# WT.net
KiCad netlist of a schematic drawn in EAGLE
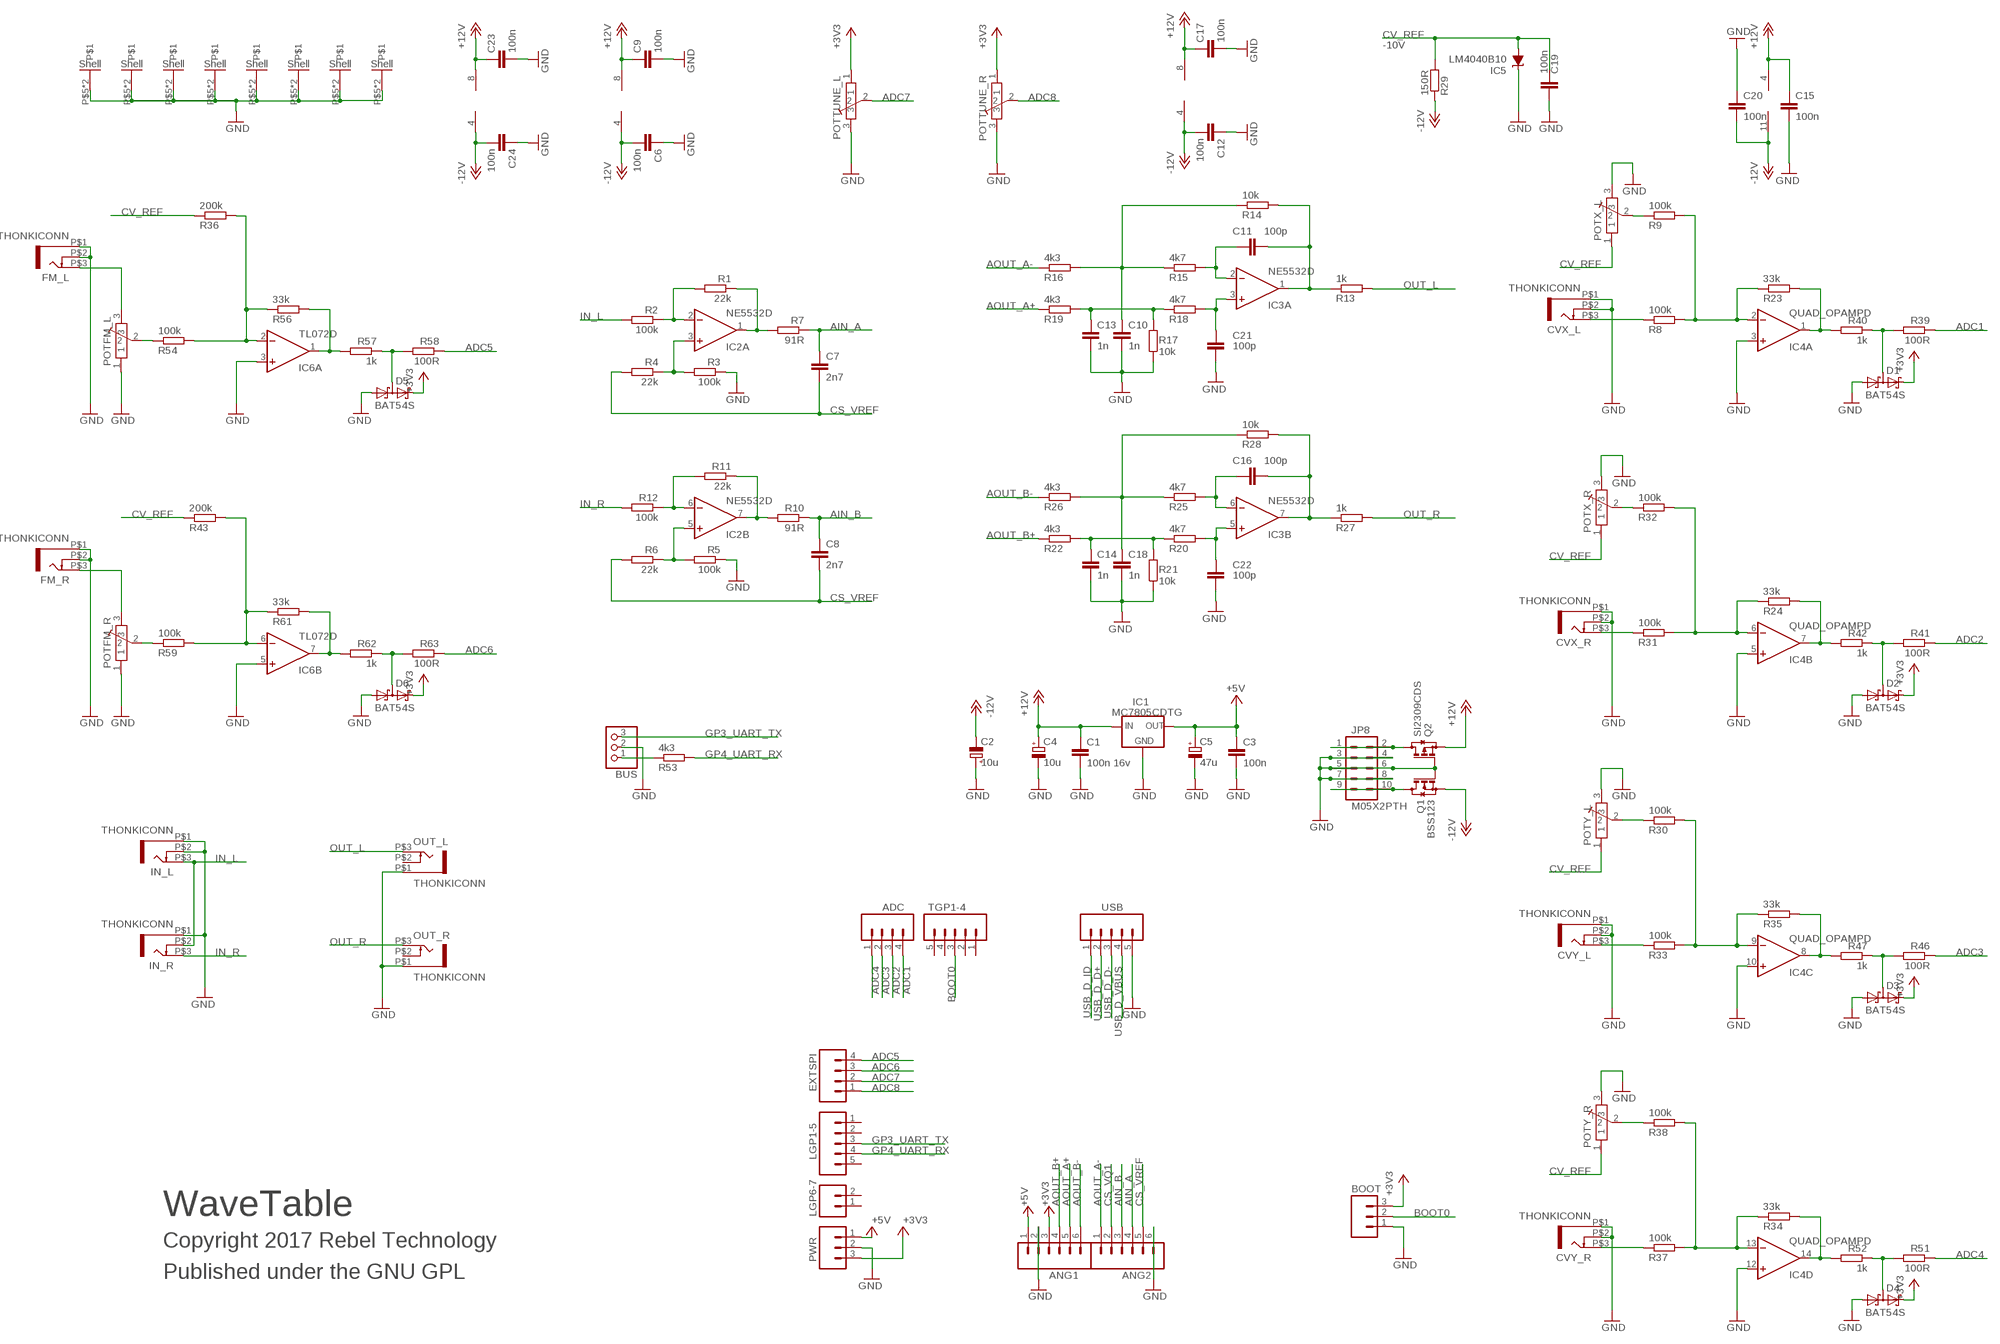
[diagram p0: schematic, sheet 1]

(export (version "E")
  (design (tool "Eeschema 10.0.6"))
  (components
    (comp (ref "ADC")
      (value "M04PTH")
      (footprint "eagle-import:1X04")
      (libsource (lib "eagle-import") (part "M04PTH"))
    )
    (comp (ref "ANG1")
      (value "M06SIP")
      (footprint "eagle-import:1X06")
      (libsource (lib "eagle-import") (part "M06SIP"))
    )
    (comp (ref "ANG2")
      (value "M06SIP")
      (footprint "eagle-import:1X06")
      (libsource (lib "eagle-import") (part "M06SIP"))
    )
    (comp (ref "BOOT")
      (value "M03PTH")
      (footprint "eagle-import:1X03")
      (libsource (lib "eagle-import") (part "M03PTH"))
    )
    (comp (ref "BUS")
      (value "CON-JST-1X03PH-TH")
      (footprint "eagle-import:JST-B3B-PH-KL")
      (libsource (lib "eagle-import") (part "CON-JST-1X03PH-TH"))
    )
    (comp (ref "C1")
      (value "100n 16v")
      (footprint "eagle-import:C0603")
      (libsource (lib "eagle-import") (part "C-EUC0603"))
    )
    (comp (ref "C2")
      (value "10u")
      (footprint "eagle-import:CPOL-5")
      (libsource (lib "eagle-import") (part "CPOL-EU153CLV-0505"))
    )
    (comp (ref "C3")
      (value "100n")
      (footprint "eagle-import:C0603")
      (libsource (lib "eagle-import") (part "C-EUC0603"))
    )
    (comp (ref "C4")
      (value "10u")
      (footprint "eagle-import:CPOL-5")
      (libsource (lib "eagle-import") (part "CPOL-EU153CLV-0505"))
    )
    (comp (ref "C5")
      (value "47u")
      (footprint "eagle-import:PANASONIC_C")
      (libsource (lib "eagle-import") (part "rcl_CPOL-EUC"))
    )
    (comp (ref "C6")
      (value "100n")
      (footprint "eagle-import:C0603")
      (libsource (lib "eagle-import") (part "resistor_C-EUC0603"))
    )
    (comp (ref "C7")
      (value "2n7")
      (footprint "eagle-import:C0603")
      (libsource (lib "eagle-import") (part "resistor_C-EUC0603"))
    )
    (comp (ref "C8")
      (value "2n7")
      (footprint "eagle-import:C0603")
      (libsource (lib "eagle-import") (part "resistor_C-EUC0603"))
    )
    (comp (ref "C9")
      (value "100n")
      (footprint "eagle-import:C0603")
      (libsource (lib "eagle-import") (part "resistor_C-EUC0603"))
    )
    (comp (ref "C10")
      (value "1n")
      (footprint "eagle-import:C0603")
      (libsource (lib "eagle-import") (part "resistor_C-EUC0603"))
    )
    (comp (ref "C11")
      (value "100p")
      (footprint "eagle-import:C0603")
      (libsource (lib "eagle-import") (part "resistor_C-EUC0603"))
    )
    (comp (ref "C12")
      (value "100n")
      (footprint "eagle-import:C0603")
      (libsource (lib "eagle-import") (part "resistor_C-EUC0603"))
    )
    (comp (ref "C13")
      (value "1n")
      (footprint "eagle-import:C0603")
      (libsource (lib "eagle-import") (part "resistor_C-EUC0603"))
    )
    (comp (ref "C14")
      (value "1n")
      (footprint "eagle-import:C0603")
      (libsource (lib "eagle-import") (part "resistor_C-EUC0603"))
    )
    (comp (ref "C15")
      (value "100n")
      (footprint "eagle-import:C0603")
      (libsource (lib "eagle-import") (part "resistor_C-EUC0603"))
    )
    (comp (ref "C16")
      (value "100p")
      (footprint "eagle-import:C0603")
      (libsource (lib "eagle-import") (part "resistor_C-EUC0603"))
    )
    (comp (ref "C17")
      (value "100n")
      (footprint "eagle-import:C0603")
      (libsource (lib "eagle-import") (part "resistor_C-EUC0603"))
    )
    (comp (ref "C18")
      (value "1n")
      (footprint "eagle-import:C0603")
      (libsource (lib "eagle-import") (part "resistor_C-EUC0603"))
    )
    (comp (ref "C19")
      (value "100n")
      (footprint "eagle-import:C0603")
      (libsource (lib "eagle-import") (part "resistor_C-EUC0603"))
    )
    (comp (ref "C20")
      (value "100n")
      (footprint "eagle-import:C0603")
      (libsource (lib "eagle-import") (part "resistor_C-EUC0603"))
    )
    (comp (ref "C21")
      (value "100p")
      (footprint "eagle-import:C0603")
      (libsource (lib "eagle-import") (part "resistor_C-EUC0603"))
    )
    (comp (ref "C22")
      (value "100p")
      (footprint "eagle-import:C0603")
      (libsource (lib "eagle-import") (part "resistor_C-EUC0603"))
    )
    (comp (ref "C23")
      (value "100n")
      (footprint "eagle-import:C0603")
      (libsource (lib "eagle-import") (part "resistor_C-EUC0603"))
    )
    (comp (ref "C24")
      (value "100n")
      (footprint "eagle-import:C0603")
      (libsource (lib "eagle-import") (part "resistor_C-EUC0603"))
    )
    (comp (ref "CVX_L")
      (value "THONKICONN")
      (footprint "eagle-import:THONKICONN")
      (libsource (lib "eagle-import") (part "THONKICONN"))
    )
    (comp (ref "CVX_R")
      (value "THONKICONN")
      (footprint "eagle-import:THONKICONN")
      (libsource (lib "eagle-import") (part "THONKICONN"))
    )
    (comp (ref "CVY_L")
      (value "THONKICONN")
      (footprint "eagle-import:THONKICONN")
      (libsource (lib "eagle-import") (part "THONKICONN"))
    )
    (comp (ref "CVY_R")
      (value "THONKICONN")
      (footprint "eagle-import:THONKICONN")
      (libsource (lib "eagle-import") (part "THONKICONN"))
    )
    (comp (ref "D1")
      (value "BAT54S")
      (footprint "eagle-import:SOT23")
      (libsource (lib "eagle-import") (part "BAT54S"))
    )
    (comp (ref "D2")
      (value "BAT54S")
      (footprint "eagle-import:SOT23")
      (libsource (lib "eagle-import") (part "BAT54S"))
    )
    (comp (ref "D3")
      (value "BAT54S")
      (footprint "eagle-import:SOT23")
      (libsource (lib "eagle-import") (part "BAT54S"))
    )
    (comp (ref "D4")
      (value "BAT54S")
      (footprint "eagle-import:SOT23")
      (libsource (lib "eagle-import") (part "BAT54S"))
    )
    (comp (ref "D5")
      (value "BAT54S")
      (footprint "eagle-import:SOT23")
      (libsource (lib "eagle-import") (part "BAT54S"))
    )
    (comp (ref "D6")
      (value "BAT54S")
      (footprint "eagle-import:SOT23")
      (libsource (lib "eagle-import") (part "BAT54S"))
    )
    (comp (ref "EXTSPI")
      (value "M04PTH")
      (footprint "eagle-import:1X04")
      (libsource (lib "eagle-import") (part "M04PTH"))
    )
    (comp (ref "FM_L")
      (value "THONKICONN")
      (footprint "eagle-import:THONKICONN")
      (libsource (lib "eagle-import") (part "THONKICONN"))
    )
    (comp (ref "FM_R")
      (value "THONKICONN")
      (footprint "eagle-import:THONKICONN")
      (libsource (lib "eagle-import") (part "THONKICONN"))
    )
    (comp (ref "IC1")
      (value "MC7805CDTG")
      (footprint "eagle-import:DPACK")
      (libsource (lib "eagle-import") (part "MC78XX"))
    )
    (comp (ref "IC2")
      (value "NE5532D")
      (footprint "eagle-import:SO08")
      (libsource (lib "eagle-import") (part "NE5532D"))
    )
    (comp (ref "IC3")
      (value "NE5532D")
      (footprint "eagle-import:SO08")
      (libsource (lib "eagle-import") (part "NE5532D"))
    )
    (comp (ref "IC4")
      (value "QUAD_OPAMPD")
      (footprint "eagle-import:SO14")
      (libsource (lib "eagle-import") (part "QUAD_OPAMPD"))
    )
    (comp (ref "IC5")
      (value "LM4040B10")
      (footprint "eagle-import:DBZ_R-PDSO-G3")
      (fields (field (name "MF") "TEXAS INSTRUMENT CONNECTORS") (field (name "MPN") "LM4041C12QDBZT"))
      (libsource (lib "eagle-import") (part "LM4041DBZC12"))
    )
    (comp (ref "IC6")
      (value "TL072D")
      (footprint "eagle-import:SO08")
      (libsource (lib "eagle-import") (part "TL072D"))
    )
    (comp (ref "IN_L")
      (value "THONKICONN")
      (footprint "eagle-import:THONKICONN")
      (libsource (lib "eagle-import") (part "THONKICONN"))
    )
    (comp (ref "IN_R")
      (value "THONKICONN")
      (footprint "eagle-import:THONKICONN")
      (libsource (lib "eagle-import") (part "THONKICONN"))
    )
    (comp (ref "JP8")
      (value "M05X2PTH")
      (footprint "eagle-import:AVR_ICSP")
      (libsource (lib "eagle-import") (part "M05X2PTH"))
    )
    (comp (ref "LGP1-5")
      (value "M05PTH")
      (footprint "eagle-import:1X05")
      (libsource (lib "eagle-import") (part "M05PTH"))
    )
    (comp (ref "LGP6-7")
      (value "M02PTH")
      (footprint "eagle-import:1X02")
      (libsource (lib "eagle-import") (part "M02PTH"))
    )
    (comp (ref "OUT_L")
      (value "THONKICONN")
      (footprint "eagle-import:THONKICONN")
      (libsource (lib "eagle-import") (part "THONKICONN"))
    )
    (comp (ref "OUT_R")
      (value "THONKICONN")
      (footprint "eagle-import:THONKICONN")
      (libsource (lib "eagle-import") (part "THONKICONN"))
    )
    (comp (ref "POTFM_L")
      (value "POT-ALPS-RK09L1140")
      (footprint "eagle-import:POT-ALPS-RK09L1140")
      (libsource (lib "eagle-import") (part "POT-ALPS-RK09L1140"))
    )
    (comp (ref "POTFM_R")
      (value "POT-ALPS-RK09L1140")
      (footprint "eagle-import:POT-ALPS-RK09L1140")
      (libsource (lib "eagle-import") (part "POT-ALPS-RK09L1140"))
    )
    (comp (ref "POTTUNE_L")
      (value "POT-ALPS-RK09L1140")
      (footprint "eagle-import:POT-ALPS-RK09L1140")
      (libsource (lib "eagle-import") (part "POT-ALPS-RK09L1140"))
    )
    (comp (ref "POTTUNE_R")
      (value "POT-ALPS-RK09L1140")
      (footprint "eagle-import:POT-ALPS-RK09L1140")
      (libsource (lib "eagle-import") (part "POT-ALPS-RK09L1140"))
    )
    (comp (ref "POTX_L")
      (value "POT-ALPS-RK09L1140")
      (footprint "eagle-import:POT-ALPS-RK09L1140")
      (libsource (lib "eagle-import") (part "POT-ALPS-RK09L1140"))
    )
    (comp (ref "POTX_R")
      (value "POT-ALPS-RK09L1140")
      (footprint "eagle-import:POT-ALPS-RK09L1140")
      (libsource (lib "eagle-import") (part "POT-ALPS-RK09L1140"))
    )
    (comp (ref "POTY_L")
      (value "POT-ALPS-RK09L1140")
      (footprint "eagle-import:POT-ALPS-RK09L1140")
      (libsource (lib "eagle-import") (part "POT-ALPS-RK09L1140"))
    )
    (comp (ref "POTY_R")
      (value "POT-ALPS-RK09L1140")
      (footprint "eagle-import:POT-ALPS-RK09L1140")
      (libsource (lib "eagle-import") (part "POT-ALPS-RK09L1140"))
    )
    (comp (ref "PWR")
      (value "M03PTH")
      (footprint "eagle-import:1X03")
      (libsource (lib "eagle-import") (part "M03PTH"))
    )
    (comp (ref "Q1")
      (value "BSS123")
      (footprint "eagle-import:SOT23")
      (libsource (lib "eagle-import") (part "BSS123"))
    )
    (comp (ref "Q2")
      (value "SI2309CDS")
      (footprint "eagle-import:SOT23")
      (libsource (lib "eagle-import") (part "BSS84"))
    )
    (comp (ref "R1")
      (value "22k")
      (footprint "eagle-import:0603")
      (libsource (lib "eagle-import") (part "R-EU_0603"))
    )
    (comp (ref "R2")
      (value "100k")
      (footprint "eagle-import:0603")
      (libsource (lib "eagle-import") (part "R-EU_0603"))
    )
    (comp (ref "R3")
      (value "100k")
      (footprint "eagle-import:0603")
      (libsource (lib "eagle-import") (part "R-EU_0603"))
    )
    (comp (ref "R4")
      (value "22k")
      (footprint "eagle-import:0603")
      (libsource (lib "eagle-import") (part "R-EU_0603"))
    )
    (comp (ref "R5")
      (value "100k")
      (footprint "eagle-import:0603")
      (libsource (lib "eagle-import") (part "R-EU_0603"))
    )
    (comp (ref "R6")
      (value "22k")
      (footprint "eagle-import:0603")
      (libsource (lib "eagle-import") (part "R-EU_0603"))
    )
    (comp (ref "R7")
      (value "91R")
      (footprint "eagle-import:0603")
      (libsource (lib "eagle-import") (part "R-EU_0603"))
    )
    (comp (ref "R8")
      (value "100k")
      (footprint "eagle-import:0603")
      (libsource (lib "eagle-import") (part "R-EU_0603"))
    )
    (comp (ref "R9")
      (value "100k")
      (footprint "eagle-import:0603")
      (libsource (lib "eagle-import") (part "R-EU_0603"))
    )
    (comp (ref "R10")
      (value "91R")
      (footprint "eagle-import:0603")
      (libsource (lib "eagle-import") (part "R-EU_0603"))
    )
    (comp (ref "R11")
      (value "22k")
      (footprint "eagle-import:0603")
      (libsource (lib "eagle-import") (part "R-EU_0603"))
    )
    (comp (ref "R12")
      (value "100k")
      (footprint "eagle-import:0603")
      (libsource (lib "eagle-import") (part "R-EU_0603"))
    )
    (comp (ref "R13")
      (value "1k")
      (footprint "eagle-import:0603")
      (libsource (lib "eagle-import") (part "R-EU_0603"))
    )
    (comp (ref "R14")
      (value "10k")
      (footprint "eagle-import:0603")
      (libsource (lib "eagle-import") (part "R-EU_0603"))
    )
    (comp (ref "R15")
      (value "4k7")
      (footprint "eagle-import:0603")
      (libsource (lib "eagle-import") (part "R-EU_0603"))
    )
    (comp (ref "R16")
      (value "4k3")
      (footprint "eagle-import:0603")
      (libsource (lib "eagle-import") (part "R-EU_0603"))
    )
    (comp (ref "R17")
      (value "10k")
      (footprint "eagle-import:0603")
      (libsource (lib "eagle-import") (part "R-EU_0603"))
    )
    (comp (ref "R18")
      (value "4k7")
      (footprint "eagle-import:0603")
      (libsource (lib "eagle-import") (part "R-EU_0603"))
    )
    (comp (ref "R19")
      (value "4k3")
      (footprint "eagle-import:0603")
      (libsource (lib "eagle-import") (part "R-EU_0603"))
    )
    (comp (ref "R20")
      (value "4k7")
      (footprint "eagle-import:0603")
      (libsource (lib "eagle-import") (part "R-EU_0603"))
    )
    (comp (ref "R21")
      (value "10k")
      (footprint "eagle-import:0603")
      (libsource (lib "eagle-import") (part "R-EU_0603"))
    )
    (comp (ref "R22")
      (value "4k3")
      (footprint "eagle-import:0603")
      (libsource (lib "eagle-import") (part "R-EU_0603"))
    )
    (comp (ref "R23")
      (value "33k")
      (footprint "eagle-import:0603")
      (libsource (lib "eagle-import") (part "R-EU_0603"))
    )
    (comp (ref "R24")
      (value "33k")
      (footprint "eagle-import:0603")
      (libsource (lib "eagle-import") (part "R-EU_0603"))
    )
    (comp (ref "R25")
      (value "4k7")
      (footprint "eagle-import:0603")
      (libsource (lib "eagle-import") (part "R-EU_0603"))
    )
    (comp (ref "R26")
      (value "4k3")
      (footprint "eagle-import:0603")
      (libsource (lib "eagle-import") (part "R-EU_0603"))
    )
    (comp (ref "R27")
      (value "1k")
      (footprint "eagle-import:0603")
      (libsource (lib "eagle-import") (part "R-EU_0603"))
    )
    (comp (ref "R28")
      (value "10k")
      (footprint "eagle-import:0603")
      (libsource (lib "eagle-import") (part "R-EU_0603"))
    )
    (comp (ref "R29")
      (value "150R")
      (footprint "eagle-import:0603")
      (libsource (lib "eagle-import") (part "R-EU_0603"))
    )
    (comp (ref "R30")
      (value "100k")
      (footprint "eagle-import:0603")
      (libsource (lib "eagle-import") (part "R-EU_0603"))
    )
    (comp (ref "R31")
      (value "100k")
      (footprint "eagle-import:0603")
      (libsource (lib "eagle-import") (part "R-EU_0603"))
    )
    (comp (ref "R32")
      (value "100k")
      (footprint "eagle-import:0603")
      (libsource (lib "eagle-import") (part "R-EU_0603"))
    )
    (comp (ref "R33")
      (value "100k")
      (footprint "eagle-import:0603")
      (libsource (lib "eagle-import") (part "R-EU_0603"))
    )
    (comp (ref "R34")
      (value "33k")
      (footprint "eagle-import:0603")
      (libsource (lib "eagle-import") (part "R-EU_0603"))
    )
    (comp (ref "R35")
      (value "33k")
      (footprint "eagle-import:0603")
      (libsource (lib "eagle-import") (part "R-EU_0603"))
    )
    (comp (ref "R36")
      (value "200k")
      (footprint "eagle-import:0603")
      (libsource (lib "eagle-import") (part "R-EU_0603"))
    )
    (comp (ref "R37")
      (value "100k")
      (footprint "eagle-import:0603")
      (libsource (lib "eagle-import") (part "R-EU_0603"))
    )
    (comp (ref "R38")
      (value "100k")
      (footprint "eagle-import:0603")
      (libsource (lib "eagle-import") (part "R-EU_0603"))
    )
    (comp (ref "R39")
      (value "100R")
      (footprint "eagle-import:0603")
      (libsource (lib "eagle-import") (part "R-EU_0603"))
    )
    (comp (ref "R40")
      (value "1k")
      (footprint "eagle-import:0603")
      (libsource (lib "eagle-import") (part "R-EU_0603"))
    )
    (comp (ref "R41")
      (value "100R")
      (footprint "eagle-import:0603")
      (libsource (lib "eagle-import") (part "R-EU_0603"))
    )
    (comp (ref "R42")
      (value "1k")
      (footprint "eagle-import:0603")
      (libsource (lib "eagle-import") (part "R-EU_0603"))
    )
    (comp (ref "R43")
      (value "200k")
      (footprint "eagle-import:0603")
      (libsource (lib "eagle-import") (part "R-EU_0603"))
    )
    (comp (ref "R46")
      (value "100R")
      (footprint "eagle-import:0603")
      (libsource (lib "eagle-import") (part "R-EU_0603"))
    )
    (comp (ref "R47")
      (value "1k")
      (footprint "eagle-import:0603")
      (libsource (lib "eagle-import") (part "R-EU_0603"))
    )
    (comp (ref "R51")
      (value "100R")
      (footprint "eagle-import:0603")
      (libsource (lib "eagle-import") (part "R-EU_0603"))
    )
    (comp (ref "R52")
      (value "1k")
      (footprint "eagle-import:0603")
      (libsource (lib "eagle-import") (part "R-EU_0603"))
    )
    (comp (ref "R53")
      (value "4k3")
      (footprint "eagle-import:0603")
      (libsource (lib "eagle-import") (part "R-EU_0603"))
    )
    (comp (ref "R54")
      (value "100k")
      (footprint "eagle-import:0603")
      (libsource (lib "eagle-import") (part "R-EU_0603"))
    )
    (comp (ref "R56")
      (value "33k")
      (footprint "eagle-import:0603")
      (libsource (lib "eagle-import") (part "R-EU_0603"))
    )
    (comp (ref "R57")
      (value "1k")
      (footprint "eagle-import:0603")
      (libsource (lib "eagle-import") (part "R-EU_0603"))
    )
    (comp (ref "R58")
      (value "100R")
      (footprint "eagle-import:0603")
      (libsource (lib "eagle-import") (part "R-EU_0603"))
    )
    (comp (ref "R59")
      (value "100k")
      (footprint "eagle-import:0603")
      (libsource (lib "eagle-import") (part "R-EU_0603"))
    )
    (comp (ref "R61")
      (value "33k")
      (footprint "eagle-import:0603")
      (libsource (lib "eagle-import") (part "R-EU_0603"))
    )
    (comp (ref "R62")
      (value "1k")
      (footprint "eagle-import:0603")
      (libsource (lib "eagle-import") (part "R-EU_0603"))
    )
    (comp (ref "R63")
      (value "100R")
      (footprint "eagle-import:0603")
      (libsource (lib "eagle-import") (part "R-EU_0603"))
    )
    (comp (ref "TGP1-4")
      (value "M05PTH")
      (footprint "eagle-import:1X05")
      (libsource (lib "eagle-import") (part "M05PTH"))
    )
    (comp (ref "USB")
      (value "M05PTH")
      (footprint "eagle-import:1X05")
      (libsource (lib "eagle-import") (part "M05PTH"))
    )
  )
  (nets
    (net (code "1") (name "+3V3") (class "Default")
      (node (ref "ANG1") (pin "3") (pinfunction "3_3") (pintype "passive"))
      (node (ref "BOOT") (pin "3") (pinfunction "3_3") (pintype "passive"))
      (node (ref "D1") (pin "2") (pinfunction "C2_2") (pintype "passive"))
      (node (ref "D2") (pin "2") (pinfunction "C2_2") (pintype "passive"))
      (node (ref "D3") (pin "2") (pinfunction "C2_2") (pintype "passive"))
      (node (ref "D4") (pin "2") (pinfunction "C2_2") (pintype "passive"))
      (node (ref "D5") (pin "2") (pinfunction "C2_2") (pintype "passive"))
      (node (ref "D6") (pin "2") (pinfunction "C2_2") (pintype "passive"))
      (node (ref "POTTUNE_L") (pin "1") (pinfunction "1_1") (pintype "bidirectional"))
      (node (ref "POTTUNE_R") (pin "1") (pinfunction "1_1") (pintype "bidirectional"))
      (node (ref "PWR") (pin "3") (pinfunction "3_3") (pintype "passive"))
    )
    (net (code "2") (name "+5V") (class "Default")
      (node (ref "ANG1") (pin "1") (pinfunction "1_1") (pintype "passive"))
      (node (ref "C3") (pin "1") (pinfunction "1_1") (pintype "passive"))
      (node (ref "C5") (pin "+") (pinfunction "+_+") (pintype "passive"))
      (node (ref "IC1") (pin "3") (pinfunction "OUT_3") (pintype "passive"))
      (node (ref "PWR") (pin "1") (pinfunction "1_1") (pintype "passive"))
    )
    (net (code "3") (name "+12V") (class "Default")
      (node (ref "C1") (pin "1") (pinfunction "1_1") (pintype "passive"))
      (node (ref "C15") (pin "1") (pinfunction "1_1") (pintype "passive"))
      (node (ref "C17") (pin "1") (pinfunction "1_1") (pintype "passive"))
      (node (ref "C23") (pin "1") (pinfunction "1_1") (pintype "passive"))
      (node (ref "C4") (pin "+") (pinfunction "+_+") (pintype "passive"))
      (node (ref "C9") (pin "1") (pinfunction "1_1") (pintype "passive"))
      (node (ref "IC1") (pin "1") (pinfunction "IN_1") (pintype "input"))
      (node (ref "IC2") (pin "8") (pinfunction "V+_8") (pintype "power_in"))
      (node (ref "IC3") (pin "8") (pinfunction "V+_8") (pintype "power_in"))
      (node (ref "IC4") (pin "4") (pinfunction "V+_4") (pintype "power_in"))
      (node (ref "IC6") (pin "8") (pinfunction "V+_8") (pintype "power_in"))
      (node (ref "Q2") (pin "2") (pinfunction "S_2") (pintype "passive"))
    )
    (net (code "4") (name "-12V") (class "Default")
      (node (ref "C12") (pin "2") (pinfunction "2_2") (pintype "passive"))
      (node (ref "C2") (pin "-") (pinfunction "-_-") (pintype "passive"))
      (node (ref "C20") (pin "2") (pinfunction "2_2") (pintype "passive"))
      (node (ref "C24") (pin "2") (pinfunction "2_2") (pintype "passive"))
      (node (ref "C6") (pin "2") (pinfunction "2_2") (pintype "passive"))
      (node (ref "IC2") (pin "4") (pinfunction "V-_4") (pintype "power_in"))
      (node (ref "IC3") (pin "4") (pinfunction "V-_4") (pintype "power_in"))
      (node (ref "IC4") (pin "11") (pinfunction "V-_11") (pintype "power_in"))
      (node (ref "IC6") (pin "4") (pinfunction "V-_4") (pintype "power_in"))
      (node (ref "Q1") (pin "2") (pinfunction "S_2") (pintype "passive"))
      (node (ref "R29") (pin "1") (pinfunction "1_1") (pintype "passive"))
    )
    (net (code "5") (name "/ADC1") (class "Default")
      (node (ref "ADC") (pin "4") (pinfunction "4_4") (pintype "passive"))
      (node (ref "R39") (pin "1") (pinfunction "1_1") (pintype "passive"))
    )
    (net (code "6") (name "/ADC2") (class "Default")
      (node (ref "ADC") (pin "3") (pinfunction "3_3") (pintype "passive"))
      (node (ref "R41") (pin "1") (pinfunction "1_1") (pintype "passive"))
    )
    (net (code "7") (name "/ADC3") (class "Default")
      (node (ref "ADC") (pin "2") (pinfunction "2_2") (pintype "passive"))
      (node (ref "R46") (pin "1") (pinfunction "1_1") (pintype "passive"))
    )
    (net (code "8") (name "/ADC4") (class "Default")
      (node (ref "ADC") (pin "1") (pinfunction "1_1") (pintype "passive"))
      (node (ref "R51") (pin "1") (pinfunction "1_1") (pintype "passive"))
    )
    (net (code "9") (name "/ADC5") (class "Default")
      (node (ref "EXTSPI") (pin "4") (pinfunction "4_4") (pintype "passive"))
      (node (ref "R58") (pin "1") (pinfunction "1_1") (pintype "passive"))
    )
    (net (code "10") (name "/ADC6") (class "Default")
      (node (ref "EXTSPI") (pin "3") (pinfunction "3_3") (pintype "passive"))
      (node (ref "R63") (pin "1") (pinfunction "1_1") (pintype "passive"))
    )
    (net (code "11") (name "/ADC7") (class "Default")
      (node (ref "EXTSPI") (pin "2") (pinfunction "2_2") (pintype "passive"))
      (node (ref "POTTUNE_L") (pin "2") (pinfunction "2_2") (pintype "bidirectional"))
    )
    (net (code "12") (name "/ADC8") (class "Default")
      (node (ref "EXTSPI") (pin "1") (pinfunction "1_1") (pintype "passive"))
      (node (ref "POTTUNE_R") (pin "2") (pinfunction "2_2") (pintype "bidirectional"))
    )
    (net (code "13") (name "/AIN_A") (class "Default")
      (node (ref "ANG2") (pin "4") (pinfunction "4_4") (pintype "passive"))
      (node (ref "C7") (pin "1") (pinfunction "1_1") (pintype "passive"))
      (node (ref "R7") (pin "1") (pinfunction "1_1") (pintype "passive"))
    )
    (net (code "14") (name "/AIN_B") (class "Default")
      (node (ref "ANG2") (pin "3") (pinfunction "3_3") (pintype "passive"))
      (node (ref "C8") (pin "1") (pinfunction "1_1") (pintype "passive"))
      (node (ref "R10") (pin "1") (pinfunction "1_1") (pintype "passive"))
    )
    (net (code "15") (name "/AOUT_A+") (class "Default")
      (node (ref "ANG1") (pin "5") (pinfunction "5_5") (pintype "passive"))
      (node (ref "R19") (pin "1") (pinfunction "1_1") (pintype "passive"))
    )
    (net (code "16") (name "/AOUT_A-") (class "Default")
      (node (ref "ANG2") (pin "1") (pinfunction "1_1") (pintype "passive"))
      (node (ref "R16") (pin "1") (pinfunction "1_1") (pintype "passive"))
    )
    (net (code "17") (name "/AOUT_B+") (class "Default")
      (node (ref "ANG1") (pin "4") (pinfunction "4_4") (pintype "passive"))
      (node (ref "R22") (pin "1") (pinfunction "1_1") (pintype "passive"))
    )
    (net (code "18") (name "/AOUT_B-") (class "Default")
      (node (ref "ANG1") (pin "6") (pinfunction "6_6") (pintype "passive"))
      (node (ref "R26") (pin "1") (pinfunction "1_1") (pintype "passive"))
    )
    (net (code "19") (name "/BOOT0") (class "Default")
      (node (ref "BOOT") (pin "2") (pinfunction "2_2") (pintype "passive"))
      (node (ref "TGP1-4") (pin "3") (pinfunction "3_3") (pintype "passive"))
    )
    (net (code "20") (name "/CS_VQ1") (class "Default")
      (node (ref "ANG2") (pin "2") (pinfunction "2_2") (pintype "passive"))
    )
    (net (code "21") (name "/CS_VREF") (class "Default")
      (node (ref "ANG2") (pin "5") (pinfunction "5_5") (pintype "passive"))
      (node (ref "C7") (pin "2") (pinfunction "2_2") (pintype "passive"))
      (node (ref "C8") (pin "2") (pinfunction "2_2") (pintype "passive"))
      (node (ref "R4") (pin "2") (pinfunction "2_2") (pintype "passive"))
      (node (ref "R6") (pin "2") (pinfunction "2_2") (pintype "passive"))
    )
    (net (code "22") (name "/CV_REF") (class "Default")
      (node (ref "C19") (pin "1") (pinfunction "1_1") (pintype "passive"))
      (node (ref "IC5") (pin "2") (pinfunction "A_2") (pintype "passive"))
      (node (ref "POTX_L") (pin "1") (pinfunction "1_1") (pintype "bidirectional"))
      (node (ref "POTX_R") (pin "1") (pinfunction "1_1") (pintype "bidirectional"))
      (node (ref "POTY_L") (pin "1") (pinfunction "1_1") (pintype "bidirectional"))
      (node (ref "POTY_R") (pin "1") (pinfunction "1_1") (pintype "bidirectional"))
      (node (ref "R29") (pin "2") (pinfunction "2_2") (pintype "passive"))
      (node (ref "R36") (pin "1") (pinfunction "1_1") (pintype "passive"))
      (node (ref "R43") (pin "1") (pinfunction "1_1") (pintype "passive"))
    )
    (net (code "23") (name "/GP3_UART_TX") (class "Default")
      (node (ref "BUS") (pin "3") (pinfunction "3_3") (pintype "passive"))
      (node (ref "LGP1-5") (pin "3") (pinfunction "3_3") (pintype "passive"))
    )
    (net (code "24") (name "/GP4_UART_RX") (class "Default")
      (node (ref "LGP1-5") (pin "4") (pinfunction "4_4") (pintype "passive"))
      (node (ref "R53") (pin "2") (pinfunction "2_2") (pintype "passive"))
    )
    (net (code "25") (name "/IN_L") (class "Default")
      (node (ref "IN_L") (pin "P$3") (pinfunction "3_P$3") (pintype "passive"))
      (node (ref "IN_R") (pin "P$2") (pinfunction "4_P$2") (pintype "passive"))
      (node (ref "R2") (pin "2") (pinfunction "2_2") (pintype "passive"))
    )
    (net (code "26") (name "/IN_R") (class "Default")
      (node (ref "IN_R") (pin "P$3") (pinfunction "3_P$3") (pintype "passive"))
      (node (ref "R12") (pin "2") (pinfunction "2_2") (pintype "passive"))
    )
    (net (code "27") (name "/OUT_L") (class "Default")
      (node (ref "OUT_L") (pin "P$3") (pinfunction "3_P$3") (pintype "passive"))
      (node (ref "R13") (pin "2") (pinfunction "2_2") (pintype "passive"))
    )
    (net (code "28") (name "/OUT_R") (class "Default")
      (node (ref "OUT_R") (pin "P$3") (pinfunction "3_P$3") (pintype "passive"))
      (node (ref "R27") (pin "2") (pinfunction "2_2") (pintype "passive"))
    )
    (net (code "29") (name "/USB_D_D+") (class "Default")
      (node (ref "USB") (pin "2") (pinfunction "2_2") (pintype "passive"))
    )
    (net (code "30") (name "/USB_D_D-") (class "Default")
      (node (ref "USB") (pin "3") (pinfunction "3_3") (pintype "passive"))
    )
    (net (code "31") (name "/USB_D_ID") (class "Default")
      (node (ref "USB") (pin "1") (pinfunction "1_1") (pintype "passive"))
    )
    (net (code "32") (name "/USB_D_VBUS") (class "Default")
      (node (ref "USB") (pin "4") (pinfunction "4_4") (pintype "passive"))
    )
    (net (code "33") (name "GND") (class "Default")
      (node (ref "ANG1") (pin "2") (pinfunction "2_2") (pintype "passive"))
      (node (ref "ANG2") (pin "6") (pinfunction "6_6") (pintype "passive"))
      (node (ref "BOOT") (pin "1") (pinfunction "1_1") (pintype "passive"))
      (node (ref "BUS") (pin "2") (pinfunction "2_2") (pintype "passive"))
      (node (ref "C1") (pin "2") (pinfunction "2_2") (pintype "passive"))
      (node (ref "C10") (pin "2") (pinfunction "2_2") (pintype "passive"))
      (node (ref "C12") (pin "1") (pinfunction "1_1") (pintype "passive"))
      (node (ref "C13") (pin "2") (pinfunction "2_2") (pintype "passive"))
      (node (ref "C14") (pin "2") (pinfunction "2_2") (pintype "passive"))
      (node (ref "C15") (pin "2") (pinfunction "2_2") (pintype "passive"))
      (node (ref "C17") (pin "2") (pinfunction "2_2") (pintype "passive"))
      (node (ref "C18") (pin "2") (pinfunction "2_2") (pintype "passive"))
      (node (ref "C19") (pin "2") (pinfunction "2_2") (pintype "passive"))
      (node (ref "C2") (pin "+") (pinfunction "+_+") (pintype "passive"))
      (node (ref "C20") (pin "1") (pinfunction "1_1") (pintype "passive"))
      (node (ref "C21") (pin "2") (pinfunction "2_2") (pintype "passive"))
      (node (ref "C22") (pin "2") (pinfunction "2_2") (pintype "passive"))
      (node (ref "C23") (pin "2") (pinfunction "2_2") (pintype "passive"))
      (node (ref "C24") (pin "1") (pinfunction "1_1") (pintype "passive"))
      (node (ref "C3") (pin "2") (pinfunction "2_2") (pintype "passive"))
      (node (ref "C4") (pin "-") (pinfunction "-_-") (pintype "passive"))
      (node (ref "C5") (pin "-") (pinfunction "-_-") (pintype "passive"))
      (node (ref "C6") (pin "1") (pinfunction "1_1") (pintype "passive"))
      (node (ref "C9") (pin "2") (pinfunction "2_2") (pintype "passive"))
      (node (ref "CVX_L") (pin "P$1") (pinfunction "5_P$1") (pintype "passive"))
      (node (ref "CVX_L") (pin "P$2") (pinfunction "4_P$2") (pintype "passive"))
      (node (ref "CVX_R") (pin "P$1") (pinfunction "5_P$1") (pintype "passive"))
      (node (ref "CVX_R") (pin "P$2") (pinfunction "4_P$2") (pintype "passive"))
      (node (ref "CVY_L") (pin "P$1") (pinfunction "5_P$1") (pintype "passive"))
      (node (ref "CVY_L") (pin "P$2") (pinfunction "4_P$2") (pintype "passive"))
      (node (ref "CVY_R") (pin "P$1") (pinfunction "5_P$1") (pintype "passive"))
      (node (ref "CVY_R") (pin "P$2") (pinfunction "4_P$2") (pintype "passive"))
      (node (ref "D1") (pin "1") (pinfunction "A1_1") (pintype "passive"))
      (node (ref "D2") (pin "1") (pinfunction "A1_1") (pintype "passive"))
      (node (ref "D3") (pin "1") (pinfunction "A1_1") (pintype "passive"))
      (node (ref "D4") (pin "1") (pinfunction "A1_1") (pintype "passive"))
      (node (ref "D5") (pin "1") (pinfunction "A1_1") (pintype "passive"))
      (node (ref "D6") (pin "1") (pinfunction "A1_1") (pintype "passive"))
      (node (ref "FM_L") (pin "P$1") (pinfunction "5_P$1") (pintype "passive"))
      (node (ref "FM_L") (pin "P$2") (pinfunction "4_P$2") (pintype "passive"))
      (node (ref "FM_R") (pin "P$1") (pinfunction "5_P$1") (pintype "passive"))
      (node (ref "FM_R") (pin "P$2") (pinfunction "4_P$2") (pintype "passive"))
      (node (ref "IC1") (pin "4") (pinfunction "GND_4") (pintype "input"))
      (node (ref "IC4") (pin "10") (pinfunction "+IN_10") (pintype "input"))
      (node (ref "IC4") (pin "12") (pinfunction "+IN_12") (pintype "input"))
      (node (ref "IC4") (pin "3") (pinfunction "+IN_3") (pintype "input"))
      (node (ref "IC4") (pin "5") (pinfunction "+IN_5") (pintype "input"))
      (node (ref "IC5") (pin "1") (pinfunction "C_1") (pintype "passive"))
      (node (ref "IC6") (pin "3") (pinfunction "+IN_3") (pintype "input"))
      (node (ref "IC6") (pin "5") (pinfunction "+IN_5") (pintype "input"))
      (node (ref "IN_L") (pin "P$1") (pinfunction "5_P$1") (pintype "passive"))
      (node (ref "IN_L") (pin "P$2") (pinfunction "4_P$2") (pintype "passive"))
      (node (ref "IN_R") (pin "P$1") (pinfunction "5_P$1") (pintype "passive"))
      (node (ref "JP8") (pin "3") (pinfunction "3_3") (pintype "passive"))
      (node (ref "JP8") (pin "4") (pinfunction "4_4") (pintype "passive"))
      (node (ref "JP8") (pin "5") (pinfunction "5_5") (pintype "passive"))
      (node (ref "JP8") (pin "6") (pinfunction "6_6") (pintype "passive"))
      (node (ref "JP8") (pin "7") (pinfunction "7_7") (pintype "passive"))
      (node (ref "JP8") (pin "8") (pinfunction "8_8") (pintype "passive"))
      (node (ref "OUT_L") (pin "P$1") (pinfunction "5_P$1") (pintype "passive"))
      (node (ref "OUT_R") (pin "P$1") (pinfunction "5_P$1") (pintype "passive"))
      (node (ref "POTFM_L") (pin "1") (pinfunction "1_1") (pintype "bidirectional"))
      (node (ref "POTFM_L") (pin "P$5") (pinfunction "P$1_P$5") (pintype "bidirectional"))
      (node (ref "POTFM_L") (pin "P$6") (pinfunction "P$1_P$6") (pintype "bidirectional"))
      (node (ref "POTFM_R") (pin "1") (pinfunction "1_1") (pintype "bidirectional"))
      (node (ref "POTFM_R") (pin "P$5") (pinfunction "P$1_P$5") (pintype "bidirectional"))
      (node (ref "POTFM_R") (pin "P$6") (pinfunction "P$1_P$6") (pintype "bidirectional"))
      (node (ref "POTTUNE_L") (pin "3") (pinfunction "3_3") (pintype "bidirectional"))
      (node (ref "POTTUNE_L") (pin "P$5") (pinfunction "P$1_P$5") (pintype "bidirectional"))
      (node (ref "POTTUNE_L") (pin "P$6") (pinfunction "P$1_P$6") (pintype "bidirectional"))
      (node (ref "POTTUNE_R") (pin "3") (pinfunction "3_3") (pintype "bidirectional"))
      (node (ref "POTTUNE_R") (pin "P$5") (pinfunction "P$1_P$5") (pintype "bidirectional"))
      (node (ref "POTTUNE_R") (pin "P$6") (pinfunction "P$1_P$6") (pintype "bidirectional"))
      (node (ref "POTX_L") (pin "3") (pinfunction "3_3") (pintype "bidirectional"))
      (node (ref "POTX_L") (pin "P$5") (pinfunction "P$1_P$5") (pintype "bidirectional"))
      (node (ref "POTX_L") (pin "P$6") (pinfunction "P$1_P$6") (pintype "bidirectional"))
      (node (ref "POTX_R") (pin "3") (pinfunction "3_3") (pintype "bidirectional"))
      (node (ref "POTX_R") (pin "P$5") (pinfunction "P$1_P$5") (pintype "bidirectional"))
      (node (ref "POTX_R") (pin "P$6") (pinfunction "P$1_P$6") (pintype "bidirectional"))
      (node (ref "POTY_L") (pin "3") (pinfunction "3_3") (pintype "bidirectional"))
      (node (ref "POTY_L") (pin "P$5") (pinfunction "P$1_P$5") (pintype "bidirectional"))
      (node (ref "POTY_L") (pin "P$6") (pinfunction "P$1_P$6") (pintype "bidirectional"))
      (node (ref "POTY_R") (pin "3") (pinfunction "3_3") (pintype "bidirectional"))
      (node (ref "POTY_R") (pin "P$5") (pinfunction "P$1_P$5") (pintype "bidirectional"))
      (node (ref "POTY_R") (pin "P$6") (pinfunction "P$1_P$6") (pintype "bidirectional"))
      (node (ref "PWR") (pin "2") (pinfunction "2_2") (pintype "passive"))
      (node (ref "Q1") (pin "1") (pinfunction "G_1") (pintype "passive"))
      (node (ref "Q2") (pin "1") (pinfunction "G_1") (pintype "passive"))
      (node (ref "R17") (pin "1") (pinfunction "1_1") (pintype "passive"))
      (node (ref "R21") (pin "1") (pinfunction "1_1") (pintype "passive"))
      (node (ref "R3") (pin "1") (pinfunction "1_1") (pintype "passive"))
      (node (ref "R5") (pin "1") (pinfunction "1_1") (pintype "passive"))
      (node (ref "USB") (pin "5") (pinfunction "5_5") (pintype "passive"))
    )
    (net (code "34") (name "Net-(BUS-Pad1)") (class "Default")
      (node (ref "BUS") (pin "1") (pinfunction "1_1") (pintype "passive"))
      (node (ref "R53") (pin "1") (pinfunction "1_1") (pintype "passive"))
    )
    (net (code "35") (name "Net-(C10-Pad1)") (class "Default")
      (node (ref "C10") (pin "1") (pinfunction "1_1") (pintype "passive"))
      (node (ref "R14") (pin "1") (pinfunction "1_1") (pintype "passive"))
      (node (ref "R15") (pin "1") (pinfunction "1_1") (pintype "passive"))
      (node (ref "R16") (pin "2") (pinfunction "2_2") (pintype "passive"))
    )
    (net (code "36") (name "Net-(C13-Pad1)") (class "Default")
      (node (ref "C13") (pin "1") (pinfunction "1_1") (pintype "passive"))
      (node (ref "R17") (pin "2") (pinfunction "2_2") (pintype "passive"))
      (node (ref "R18") (pin "1") (pinfunction "1_1") (pintype "passive"))
      (node (ref "R19") (pin "2") (pinfunction "2_2") (pintype "passive"))
    )
    (net (code "37") (name "Net-(C14-Pad1)") (class "Default")
      (node (ref "C14") (pin "1") (pinfunction "1_1") (pintype "passive"))
      (node (ref "R20") (pin "1") (pinfunction "1_1") (pintype "passive"))
      (node (ref "R21") (pin "2") (pinfunction "2_2") (pintype "passive"))
      (node (ref "R22") (pin "2") (pinfunction "2_2") (pintype "passive"))
    )
    (net (code "38") (name "Net-(C18-Pad1)") (class "Default")
      (node (ref "C18") (pin "1") (pinfunction "1_1") (pintype "passive"))
      (node (ref "R25") (pin "1") (pinfunction "1_1") (pintype "passive"))
      (node (ref "R26") (pin "2") (pinfunction "2_2") (pintype "passive"))
      (node (ref "R28") (pin "1") (pinfunction "1_1") (pintype "passive"))
    )
    (net (code "39") (name "Net-(CVX_L-3)") (class "Default")
      (node (ref "CVX_L") (pin "P$3") (pinfunction "3_P$3") (pintype "passive"))
      (node (ref "R8") (pin "1") (pinfunction "1_1") (pintype "passive"))
    )
    (net (code "40") (name "Net-(CVX_R-3)") (class "Default")
      (node (ref "CVX_R") (pin "P$3") (pinfunction "3_P$3") (pintype "passive"))
      (node (ref "R31") (pin "1") (pinfunction "1_1") (pintype "passive"))
    )
    (net (code "41") (name "Net-(CVY_L-3)") (class "Default")
      (node (ref "CVY_L") (pin "P$3") (pinfunction "3_P$3") (pintype "passive"))
      (node (ref "R33") (pin "1") (pinfunction "1_1") (pintype "passive"))
    )
    (net (code "42") (name "Net-(CVY_R-3)") (class "Default")
      (node (ref "CVY_R") (pin "P$3") (pinfunction "3_P$3") (pintype "passive"))
      (node (ref "R37") (pin "1") (pinfunction "1_1") (pintype "passive"))
    )
    (net (code "43") (name "Net-(D1-C1A2)") (class "Default")
      (node (ref "D1") (pin "3") (pinfunction "C1A2_3") (pintype "passive"))
      (node (ref "R39") (pin "2") (pinfunction "2_2") (pintype "passive"))
      (node (ref "R40") (pin "1") (pinfunction "1_1") (pintype "passive"))
    )
    (net (code "44") (name "Net-(D2-C1A2)") (class "Default")
      (node (ref "D2") (pin "3") (pinfunction "C1A2_3") (pintype "passive"))
      (node (ref "R41") (pin "2") (pinfunction "2_2") (pintype "passive"))
      (node (ref "R42") (pin "1") (pinfunction "1_1") (pintype "passive"))
    )
    (net (code "45") (name "Net-(D3-C1A2)") (class "Default")
      (node (ref "D3") (pin "3") (pinfunction "C1A2_3") (pintype "passive"))
      (node (ref "R46") (pin "2") (pinfunction "2_2") (pintype "passive"))
      (node (ref "R47") (pin "1") (pinfunction "1_1") (pintype "passive"))
    )
    (net (code "46") (name "Net-(D4-C1A2)") (class "Default")
      (node (ref "D4") (pin "3") (pinfunction "C1A2_3") (pintype "passive"))
      (node (ref "R51") (pin "2") (pinfunction "2_2") (pintype "passive"))
      (node (ref "R52") (pin "1") (pinfunction "1_1") (pintype "passive"))
    )
    (net (code "47") (name "Net-(D5-C1A2)") (class "Default")
      (node (ref "D5") (pin "3") (pinfunction "C1A2_3") (pintype "passive"))
      (node (ref "R57") (pin "1") (pinfunction "1_1") (pintype "passive"))
      (node (ref "R58") (pin "2") (pinfunction "2_2") (pintype "passive"))
    )
    (net (code "48") (name "Net-(D6-C1A2)") (class "Default")
      (node (ref "D6") (pin "3") (pinfunction "C1A2_3") (pintype "passive"))
      (node (ref "R62") (pin "1") (pinfunction "1_1") (pintype "passive"))
      (node (ref "R63") (pin "2") (pinfunction "2_2") (pintype "passive"))
    )
    (net (code "49") (name "Net-(FM_L-3)") (class "Default")
      (node (ref "FM_L") (pin "P$3") (pinfunction "3_P$3") (pintype "passive"))
      (node (ref "POTFM_L") (pin "3") (pinfunction "3_3") (pintype "bidirectional"))
    )
    (net (code "50") (name "Net-(FM_R-3)") (class "Default")
      (node (ref "FM_R") (pin "P$3") (pinfunction "3_P$3") (pintype "passive"))
      (node (ref "POTFM_R") (pin "3") (pinfunction "3_3") (pintype "bidirectional"))
    )
    (net (code "51") (name "Net-(IC2A-+IN)") (class "Default")
      (node (ref "IC2") (pin "3") (pinfunction "+IN_3") (pintype "input"))
      (node (ref "R3") (pin "2") (pinfunction "2_2") (pintype "passive"))
      (node (ref "R4") (pin "1") (pinfunction "1_1") (pintype "passive"))
    )
    (net (code "52") (name "Net-(IC2A--IN)") (class "Default")
      (node (ref "IC2") (pin "2") (pinfunction "-IN_2") (pintype "input"))
      (node (ref "R1") (pin "2") (pinfunction "2_2") (pintype "passive"))
      (node (ref "R2") (pin "1") (pinfunction "1_1") (pintype "passive"))
    )
    (net (code "53") (name "Net-(IC2A-OUT)") (class "Default")
      (node (ref "IC2") (pin "1") (pinfunction "OUT_1") (pintype "output"))
      (node (ref "R1") (pin "1") (pinfunction "1_1") (pintype "passive"))
      (node (ref "R7") (pin "2") (pinfunction "2_2") (pintype "passive"))
    )
    (net (code "54") (name "Net-(IC2B-+IN)") (class "Default")
      (node (ref "IC2") (pin "5") (pinfunction "+IN_5") (pintype "input"))
      (node (ref "R5") (pin "2") (pinfunction "2_2") (pintype "passive"))
      (node (ref "R6") (pin "1") (pinfunction "1_1") (pintype "passive"))
    )
    (net (code "55") (name "Net-(IC2B--IN)") (class "Default")
      (node (ref "IC2") (pin "6") (pinfunction "-IN_6") (pintype "input"))
      (node (ref "R11") (pin "2") (pinfunction "2_2") (pintype "passive"))
      (node (ref "R12") (pin "1") (pinfunction "1_1") (pintype "passive"))
    )
    (net (code "56") (name "Net-(IC2B-OUT)") (class "Default")
      (node (ref "IC2") (pin "7") (pinfunction "OUT_7") (pintype "output"))
      (node (ref "R10") (pin "2") (pinfunction "2_2") (pintype "passive"))
      (node (ref "R11") (pin "1") (pinfunction "1_1") (pintype "passive"))
    )
    (net (code "57") (name "Net-(IC3A-+IN)") (class "Default")
      (node (ref "C21") (pin "1") (pinfunction "1_1") (pintype "passive"))
      (node (ref "IC3") (pin "3") (pinfunction "+IN_3") (pintype "input"))
      (node (ref "R18") (pin "2") (pinfunction "2_2") (pintype "passive"))
    )
    (net (code "58") (name "Net-(IC3A--IN)") (class "Default")
      (node (ref "C11") (pin "1") (pinfunction "1_1") (pintype "passive"))
      (node (ref "IC3") (pin "2") (pinfunction "-IN_2") (pintype "input"))
      (node (ref "R15") (pin "2") (pinfunction "2_2") (pintype "passive"))
    )
    (net (code "59") (name "Net-(IC3A-OUT)") (class "Default")
      (node (ref "C11") (pin "2") (pinfunction "2_2") (pintype "passive"))
      (node (ref "IC3") (pin "1") (pinfunction "OUT_1") (pintype "output"))
      (node (ref "R13") (pin "1") (pinfunction "1_1") (pintype "passive"))
      (node (ref "R14") (pin "2") (pinfunction "2_2") (pintype "passive"))
    )
    (net (code "60") (name "Net-(IC3B-+IN)") (class "Default")
      (node (ref "C22") (pin "1") (pinfunction "1_1") (pintype "passive"))
      (node (ref "IC3") (pin "5") (pinfunction "+IN_5") (pintype "input"))
      (node (ref "R20") (pin "2") (pinfunction "2_2") (pintype "passive"))
    )
    (net (code "61") (name "Net-(IC3B--IN)") (class "Default")
      (node (ref "C16") (pin "1") (pinfunction "1_1") (pintype "passive"))
      (node (ref "IC3") (pin "6") (pinfunction "-IN_6") (pintype "input"))
      (node (ref "R25") (pin "2") (pinfunction "2_2") (pintype "passive"))
    )
    (net (code "62") (name "Net-(IC3B-OUT)") (class "Default")
      (node (ref "C16") (pin "2") (pinfunction "2_2") (pintype "passive"))
      (node (ref "IC3") (pin "7") (pinfunction "OUT_7") (pintype "output"))
      (node (ref "R27") (pin "1") (pinfunction "1_1") (pintype "passive"))
      (node (ref "R28") (pin "2") (pinfunction "2_2") (pintype "passive"))
    )
    (net (code "63") (name "Net-(IC4A--IN)") (class "Default")
      (node (ref "IC4") (pin "2") (pinfunction "-IN_2") (pintype "input"))
      (node (ref "R23") (pin "1") (pinfunction "1_1") (pintype "passive"))
      (node (ref "R8") (pin "2") (pinfunction "2_2") (pintype "passive"))
      (node (ref "R9") (pin "2") (pinfunction "2_2") (pintype "passive"))
    )
    (net (code "64") (name "Net-(IC4A-OUT)") (class "Default")
      (node (ref "IC4") (pin "1") (pinfunction "OUT_1") (pintype "output"))
      (node (ref "R23") (pin "2") (pinfunction "2_2") (pintype "passive"))
      (node (ref "R40") (pin "2") (pinfunction "2_2") (pintype "passive"))
    )
    (net (code "65") (name "Net-(IC4B--IN)") (class "Default")
      (node (ref "IC4") (pin "6") (pinfunction "-IN_6") (pintype "input"))
      (node (ref "R24") (pin "1") (pinfunction "1_1") (pintype "passive"))
      (node (ref "R31") (pin "2") (pinfunction "2_2") (pintype "passive"))
      (node (ref "R32") (pin "2") (pinfunction "2_2") (pintype "passive"))
    )
    (net (code "66") (name "Net-(IC4B-OUT)") (class "Default")
      (node (ref "IC4") (pin "7") (pinfunction "OUT_7") (pintype "output"))
      (node (ref "R24") (pin "2") (pinfunction "2_2") (pintype "passive"))
      (node (ref "R42") (pin "2") (pinfunction "2_2") (pintype "passive"))
    )
    (net (code "67") (name "Net-(IC4C--IN)") (class "Default")
      (node (ref "IC4") (pin "9") (pinfunction "-IN_9") (pintype "input"))
      (node (ref "R30") (pin "2") (pinfunction "2_2") (pintype "passive"))
      (node (ref "R33") (pin "2") (pinfunction "2_2") (pintype "passive"))
      (node (ref "R35") (pin "1") (pinfunction "1_1") (pintype "passive"))
    )
    (net (code "68") (name "Net-(IC4C-OUT)") (class "Default")
      (node (ref "IC4") (pin "8") (pinfunction "OUT_8") (pintype "output"))
      (node (ref "R35") (pin "2") (pinfunction "2_2") (pintype "passive"))
      (node (ref "R47") (pin "2") (pinfunction "2_2") (pintype "passive"))
    )
    (net (code "69") (name "Net-(IC4D--IN)") (class "Default")
      (node (ref "IC4") (pin "13") (pinfunction "-IN_13") (pintype "input"))
      (node (ref "R34") (pin "1") (pinfunction "1_1") (pintype "passive"))
      (node (ref "R37") (pin "2") (pinfunction "2_2") (pintype "passive"))
      (node (ref "R38") (pin "2") (pinfunction "2_2") (pintype "passive"))
    )
    (net (code "70") (name "Net-(IC4D-OUT)") (class "Default")
      (node (ref "IC4") (pin "14") (pinfunction "OUT_14") (pintype "output"))
      (node (ref "R34") (pin "2") (pinfunction "2_2") (pintype "passive"))
      (node (ref "R52") (pin "2") (pinfunction "2_2") (pintype "passive"))
    )
    (net (code "71") (name "Net-(IC6A--IN)") (class "Default")
      (node (ref "IC6") (pin "2") (pinfunction "-IN_2") (pintype "input"))
      (node (ref "R36") (pin "2") (pinfunction "2_2") (pintype "passive"))
      (node (ref "R54") (pin "2") (pinfunction "2_2") (pintype "passive"))
      (node (ref "R56") (pin "1") (pinfunction "1_1") (pintype "passive"))
    )
    (net (code "72") (name "Net-(IC6A-OUT)") (class "Default")
      (node (ref "IC6") (pin "1") (pinfunction "OUT_1") (pintype "output"))
      (node (ref "R56") (pin "2") (pinfunction "2_2") (pintype "passive"))
      (node (ref "R57") (pin "2") (pinfunction "2_2") (pintype "passive"))
    )
    (net (code "73") (name "Net-(IC6B--IN)") (class "Default")
      (node (ref "IC6") (pin "6") (pinfunction "-IN_6") (pintype "input"))
      (node (ref "R43") (pin "2") (pinfunction "2_2") (pintype "passive"))
      (node (ref "R59") (pin "2") (pinfunction "2_2") (pintype "passive"))
      (node (ref "R61") (pin "1") (pinfunction "1_1") (pintype "passive"))
    )
    (net (code "74") (name "Net-(IC6B-OUT)") (class "Default")
      (node (ref "IC6") (pin "7") (pinfunction "OUT_7") (pintype "output"))
      (node (ref "R61") (pin "2") (pinfunction "2_2") (pintype "passive"))
      (node (ref "R62") (pin "2") (pinfunction "2_2") (pintype "passive"))
    )
    (net (code "75") (name "Net-(POTFM_L-Pad2)") (class "Default")
      (node (ref "POTFM_L") (pin "2") (pinfunction "2_2") (pintype "bidirectional"))
      (node (ref "R54") (pin "1") (pinfunction "1_1") (pintype "passive"))
    )
    (net (code "76") (name "Net-(POTFM_R-Pad2)") (class "Default")
      (node (ref "POTFM_R") (pin "2") (pinfunction "2_2") (pintype "bidirectional"))
      (node (ref "R59") (pin "1") (pinfunction "1_1") (pintype "passive"))
    )
    (net (code "77") (name "Net-(POTX_L-Pad2)") (class "Default")
      (node (ref "POTX_L") (pin "2") (pinfunction "2_2") (pintype "bidirectional"))
      (node (ref "R9") (pin "1") (pinfunction "1_1") (pintype "passive"))
    )
    (net (code "78") (name "Net-(POTX_R-Pad2)") (class "Default")
      (node (ref "POTX_R") (pin "2") (pinfunction "2_2") (pintype "bidirectional"))
      (node (ref "R32") (pin "1") (pinfunction "1_1") (pintype "passive"))
    )
    (net (code "79") (name "Net-(POTY_L-Pad2)") (class "Default")
      (node (ref "POTY_L") (pin "2") (pinfunction "2_2") (pintype "bidirectional"))
      (node (ref "R30") (pin "1") (pinfunction "1_1") (pintype "passive"))
    )
    (net (code "80") (name "Net-(POTY_R-Pad2)") (class "Default")
      (node (ref "POTY_R") (pin "2") (pinfunction "2_2") (pintype "bidirectional"))
      (node (ref "R38") (pin "1") (pinfunction "1_1") (pintype "passive"))
    )
    (net (code "81") (name "Net-(Q1-D)") (class "Default")
      (node (ref "JP8") (pin "10") (pinfunction "10_10") (pintype "passive"))
      (node (ref "JP8") (pin "9") (pinfunction "9_9") (pintype "passive"))
      (node (ref "Q1") (pin "3") (pinfunction "D_3") (pintype "passive"))
    )
    (net (code "82") (name "Net-(Q2-D)") (class "Default")
      (node (ref "JP8") (pin "1") (pinfunction "1_1") (pintype "passive"))
      (node (ref "JP8") (pin "2") (pinfunction "2_2") (pintype "passive"))
      (node (ref "Q2") (pin "3") (pinfunction "D_3") (pintype "passive"))
    )
    (net (code "83") (name "unconnected-(LGP1-5-Pad1)") (class "Default")
      (node (ref "LGP1-5") (pin "1") (pinfunction "1_1") (pintype "passive"))
    )
    (net (code "84") (name "unconnected-(LGP1-5-Pad2)") (class "Default")
      (node (ref "LGP1-5") (pin "2") (pinfunction "2_2") (pintype "passive"))
    )
    (net (code "85") (name "unconnected-(LGP1-5-Pad5)") (class "Default")
      (node (ref "LGP1-5") (pin "5") (pinfunction "5_5") (pintype "passive"))
    )
    (net (code "86") (name "unconnected-(LGP6-7-Pad1)") (class "Default")
      (node (ref "LGP6-7") (pin "1") (pinfunction "1_1") (pintype "passive"))
    )
    (net (code "87") (name "unconnected-(LGP6-7-Pad2)") (class "Default")
      (node (ref "LGP6-7") (pin "2") (pinfunction "2_2") (pintype "passive"))
    )
    (net (code "88") (name "unconnected-(OUT_L-4-PadP$2)") (class "Default")
      (node (ref "OUT_L") (pin "P$2") (pinfunction "4_P$2") (pintype "passive"))
    )
    (net (code "89") (name "unconnected-(OUT_R-4-PadP$2)") (class "Default")
      (node (ref "OUT_R") (pin "P$2") (pinfunction "4_P$2") (pintype "passive"))
    )
    (net (code "90") (name "unconnected-(TGP1-4-Pad1)") (class "Default")
      (node (ref "TGP1-4") (pin "1") (pinfunction "1_1") (pintype "passive"))
    )
    (net (code "91") (name "unconnected-(TGP1-4-Pad2)") (class "Default")
      (node (ref "TGP1-4") (pin "2") (pinfunction "2_2") (pintype "passive"))
    )
    (net (code "92") (name "unconnected-(TGP1-4-Pad4)") (class "Default")
      (node (ref "TGP1-4") (pin "4") (pinfunction "4_4") (pintype "passive"))
    )
    (net (code "93") (name "unconnected-(TGP1-4-Pad5)") (class "Default")
      (node (ref "TGP1-4") (pin "5") (pinfunction "5_5") (pintype "passive"))
    )
  )
)
